# USB.net
KiCad netlist of a schematic drawn in Altium Designer
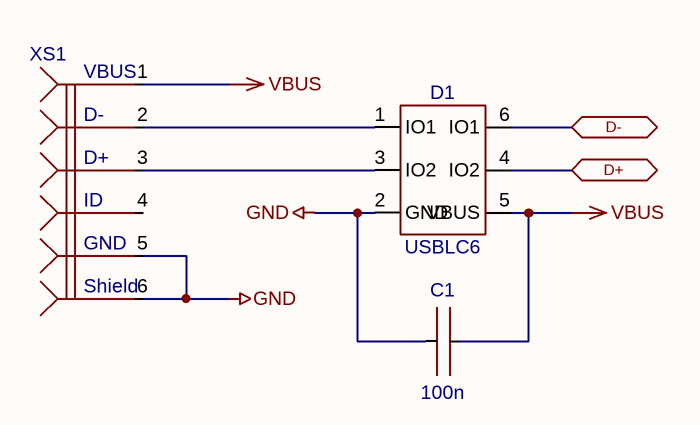
[diagram p0: USB.SchDoc]

(export (version "E")
  (design (tool "Eeschema 10.0.6"))
  (components
    (comp (ref "C1")
      (value "100n")
      (footprint "CAPC1608X09N")
      (description "GRM188R71E104KA01D")
      (libsource (lib "Capasitors") (part "C0603-100n-25V-X7R-10%"))
    )
    (comp (ref "D1")
      (value "USBLC6")
      (footprint "STM SOT23-6L")
      (libsource (lib "Integrated Circuits") (part "USBLC6-2SC6"))
    )
    (comp (ref "XS1")
      (value "MOLEX 1050170001")
      (footprint "MOLEX 1050170001")
      (libsource (lib "Connectors") (part "MOLEX 1050170001"))
    )
  )
  (nets
    (net (code "1") (name "/D+") (class "Default")
      (node (ref "D1") (pin "4") (pinfunction "IO2_4") (pintype "passive"))
    )
    (net (code "2") (name "/D-") (class "Default")
      (node (ref "D1") (pin "6") (pinfunction "IO1_6") (pintype "passive"))
    )
    (net (code "3") (name "GND") (class "Default")
      (node (ref "C1") (pin "1") (pinfunction "1_1") (pintype "passive"))
      (node (ref "D1") (pin "2") (pinfunction "GND_2") (pintype "passive"))
      (node (ref "XS1") (pin "5") (pinfunction "GND_5") (pintype "passive"))
      (node (ref "XS1") (pin "6") (pinfunction "SHIELD_6") (pintype "passive"))
    )
    (net (code "4") (name "Net-(XS1-D+)") (class "Default")
      (node (ref "D1") (pin "3") (pinfunction "IO2_3") (pintype "passive"))
      (node (ref "XS1") (pin "3") (pinfunction "D+_3") (pintype "passive"))
    )
    (net (code "5") (name "Net-(XS1-D-)") (class "Default")
      (node (ref "D1") (pin "1") (pinfunction "IO1_1") (pintype "passive"))
      (node (ref "XS1") (pin "2") (pinfunction "D-_2") (pintype "passive"))
    )
    (net (code "6") (name "VBUS") (class "Default")
      (node (ref "C1") (pin "2") (pinfunction "2_2") (pintype "passive"))
      (node (ref "D1") (pin "5") (pinfunction "VBUS_5") (pintype "passive"))
      (node (ref "XS1") (pin "1") (pinfunction "VBUS_1") (pintype "passive"))
    )
    (net (code "7") (name "unconnected-(XS1-ID-Pad4)") (class "Default")
      (node (ref "XS1") (pin "4") (pinfunction "ID_4") (pintype "passive"))
    )
  )
)
